# PM_Drive_UI.net
KiCad netlist of a schematic drawn in Altium Designer
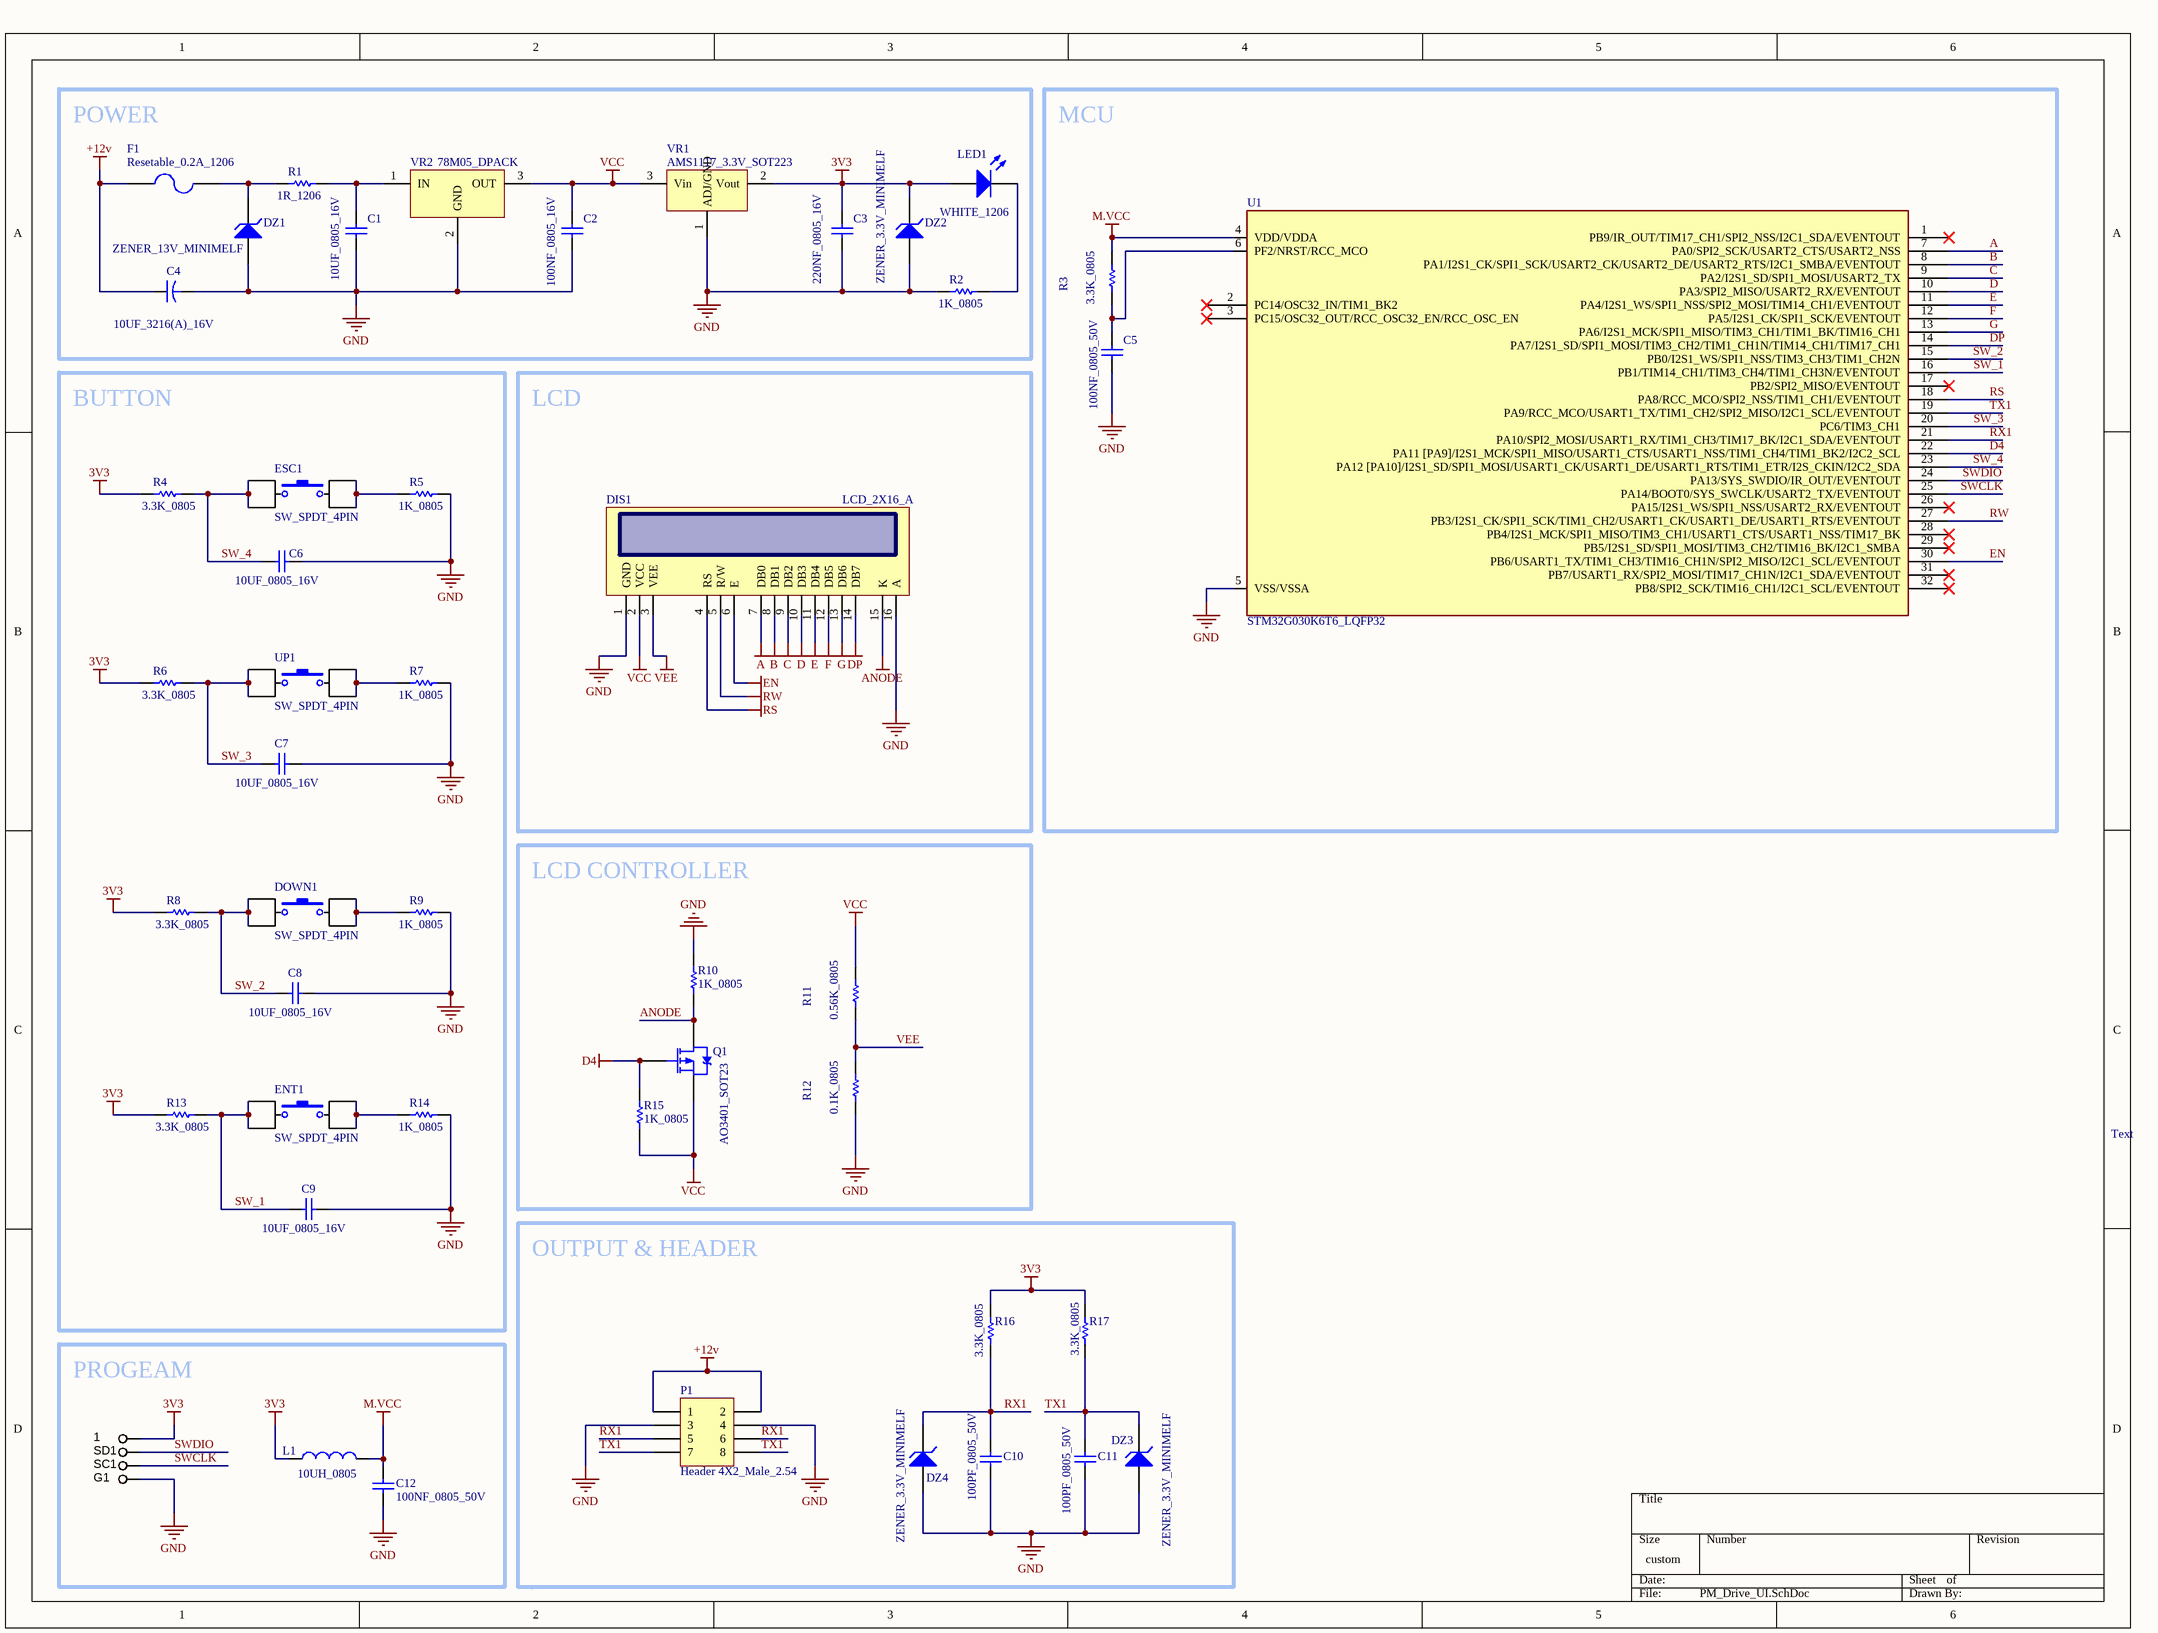
[diagram p0: PM_Drive_UI.SchDoc]

(export (version "E")
  (design (tool "Eeschema 10.0.6"))
  (components
    (comp (ref "1")
      (value "~")
      (footprint "TPSMD_D1")
      (description "TEST POINT")
      (fields (field (name "MANF") "MANF") (field (name "MANF_P#") "MANF_P#"))
      (libsource (lib "GTC Schematic") (part "TESTPOINT_SMD"))
    )
    (comp (ref "C1")
      (value "10UF_0805_16V")
      (footprint "Cap_0805_Nominal")
      (libsource (lib "Saeed_New_Lib") (part "Cap"))
    )
    (comp (ref "C2")
      (value "100NF_0805_16V")
      (footprint "Cap_0805_Nominal")
      (libsource (lib "Saeed_New_Lib") (part "Cap"))
    )
    (comp (ref "C3")
      (value "220NF_0805_16V")
      (footprint "Cap_0805_Nominal")
      (libsource (lib "Saeed_New_Lib") (part "Cap"))
    )
    (comp (ref "C4")
      (value "10UF_3216(A)_16V")
      (footprint "Cap_Tantal(3216)_A")
      (libsource (lib "GTC Shem") (part "Cap_Electrical"))
    )
    (comp (ref "C5")
      (value "100NF_0805_50V")
      (footprint "Cap_0805_Nominal")
      (libsource (lib "Saeed_New_Lib") (part "Cap"))
    )
    (comp (ref "C6")
      (value "10UF_0805_16V")
      (footprint "Cap_0805_Nominal")
      (libsource (lib "Saeed_New_Lib") (part "Cap"))
    )
    (comp (ref "C7")
      (value "10UF_0805_16V")
      (footprint "Cap_0805_Nominal")
      (libsource (lib "Saeed_New_Lib") (part "Cap"))
    )
    (comp (ref "C8")
      (value "10UF_0805_16V")
      (footprint "Cap_0805_Nominal")
      (libsource (lib "Saeed_New_Lib") (part "Cap"))
    )
    (comp (ref "C9")
      (value "10UF_0805_16V")
      (footprint "Cap_0805_Nominal")
      (libsource (lib "Saeed_New_Lib") (part "Cap"))
    )
    (comp (ref "C10")
      (value "100PF_0805_50V")
      (footprint "Cap_0805_Nominal")
      (libsource (lib "Saeed_New_Lib") (part "Cap"))
    )
    (comp (ref "C11")
      (value "100PF_0805_50V")
      (footprint "Cap_0805_Nominal")
      (libsource (lib "Saeed_New_Lib") (part "Cap"))
    )
    (comp (ref "C12")
      (value "100NF_0805_50V")
      (footprint "Cap_0805_Nominal")
      (libsource (lib "Saeed_New_Lib") (part "Cap"))
    )
    (comp (ref "DIS1")
      (value "LCD_2X16_A")
      (footprint "LCD_2X16_A")
      (libsource (lib "Amirreza") (part "LCD_2X16_A"))
    )
    (comp (ref "DOWN1")
      (value "SW_SPDT_4PIN")
      (footprint "SWPBS-DIP_6X6X13.5")
      (libsource (lib "Amirreza") (part "SW_SPDT_4PIN"))
    )
    (comp (ref "DZ1")
      (value "ZENER_13V_MINIMELF")
      (footprint "Diode_ZENER_MINIMELF")
      (libsource (lib "Amirreza") (part "Diode_Zener"))
    )
    (comp (ref "DZ2")
      (value "ZENER_3.3V_MINIMELF")
      (footprint "Diode_ZENER_MINIMELF")
      (libsource (lib "Amirreza") (part "Diode_Zener"))
    )
    (comp (ref "DZ3")
      (value "ZENER_3.3V_MINIMELF")
      (footprint "Diode_ZENER_MINIMELF")
      (libsource (lib "Amirreza") (part "Diode_Zener"))
    )
    (comp (ref "DZ4")
      (value "ZENER_3.3V_MINIMELF")
      (footprint "Diode_ZENER_MINIMELF")
      (libsource (lib "Amirreza") (part "Diode_Zener"))
    )
    (comp (ref "ENT1")
      (value "SW_SPDT_4PIN")
      (footprint "SWPBS-DIP_6X6X13.5")
      (libsource (lib "Amirreza") (part "SW_SPDT_4PIN"))
    )
    (comp (ref "ESC1")
      (value "SW_SPDT_4PIN")
      (footprint "SWPBS-DIP_6X6X13.5")
      (libsource (lib "Amirreza") (part "SW_SPDT_4PIN"))
    )
    (comp (ref "F1")
      (value "Resetable_0.2A_1206")
      (footprint "FUSE_1206")
      (libsource (lib "Amirreza") (part "FUSE"))
    )
    (comp (ref "G1")
      (value "~")
      (footprint "TPSMD_D1")
      (description "TEST POINT")
      (fields (field (name "MANF") "MANF") (field (name "MANF_P#") "MANF_P#"))
      (libsource (lib "GTC Schematic") (part "TESTPOINT_SMD"))
    )
    (comp (ref "L1")
      (value "10UH_0805")
      (footprint "INDUCTOR_0805_Nominal")
      (libsource (lib "Saeed_New_Lib") (part "Inductor"))
    )
    (comp (ref "LED1")
      (value "WHITE_1206")
      (footprint "LED_1206_NOMINAL")
      (libsource (lib "GTC Shem") (part "LED"))
    )
    (comp (ref "P1")
      (value "Header 4X2_Male_2.54")
      (footprint "HDR_M_2X4_2.54MM")
      (description "Header, 6-Pin, Dual row")
      (fields (field (name "PUBLISHER") "Altium Limited"))
      (libsource (lib "Amirreza") (part "Header 4X2"))
    )
    (comp (ref "Q1")
      (value "AO3401_SOT23")
      (footprint "SOT23_MOSFET")
      (description "P-Channel MOSFET")
      (fields (field (name "PUBLISHER") "Altium Limited"))
      (libsource (lib "Amirreza") (part "MOSFET-P"))
    )
    (comp (ref "R1")
      (value "1R_1206")
      (footprint "Res_1206_BIG SIZE")
      (libsource (lib "Amir_Library") (part "RES"))
    )
    (comp (ref "R2")
      (value "1K_0805")
      (footprint "Res_0805_Nominal")
      (libsource (lib "Amir_Library") (part "RES"))
    )
    (comp (ref "R3")
      (value "3.3K_0805")
      (footprint "Res_0805_Nominal")
      (libsource (lib "Amir_Library") (part "RES"))
    )
    (comp (ref "R4")
      (value "3.3K_0805")
      (footprint "Res_0805_Nominal")
      (libsource (lib "Amir_Library") (part "RES"))
    )
    (comp (ref "R5")
      (value "1K_0805")
      (footprint "Res_0805_Nominal")
      (libsource (lib "Amir_Library") (part "RES"))
    )
    (comp (ref "R6")
      (value "3.3K_0805")
      (footprint "Res_0805_Nominal")
      (libsource (lib "Amir_Library") (part "RES"))
    )
    (comp (ref "R7")
      (value "1K_0805")
      (footprint "Res_0805_Nominal")
      (libsource (lib "Amir_Library") (part "RES"))
    )
    (comp (ref "R8")
      (value "3.3K_0805")
      (footprint "Res_0805_Nominal")
      (libsource (lib "Amir_Library") (part "RES"))
    )
    (comp (ref "R9")
      (value "1K_0805")
      (footprint "Res_0805_Nominal")
      (libsource (lib "Amir_Library") (part "RES"))
    )
    (comp (ref "R10")
      (value "1K_0805")
      (footprint "Res_0805_Nominal")
      (libsource (lib "Amir_Library") (part "RES"))
    )
    (comp (ref "R11")
      (value "0.56K_0805")
      (footprint "Res_0805_Nominal")
      (libsource (lib "Amir_Library") (part "RES"))
    )
    (comp (ref "R12")
      (value "0.1K_0805")
      (footprint "Res_0805_Nominal")
      (libsource (lib "Amir_Library") (part "RES"))
    )
    (comp (ref "R13")
      (value "3.3K_0805")
      (footprint "Res_0805_Nominal")
      (libsource (lib "Amir_Library") (part "RES"))
    )
    (comp (ref "R14")
      (value "1K_0805")
      (footprint "Res_0805_Nominal")
      (libsource (lib "Amir_Library") (part "RES"))
    )
    (comp (ref "R15")
      (value "1K_0805")
      (footprint "Res_0805_Nominal")
      (libsource (lib "Amir_Library") (part "RES"))
    )
    (comp (ref "R16")
      (value "3.3K_0805")
      (footprint "Res_0805_Nominal")
      (libsource (lib "Amir_Library") (part "RES"))
    )
    (comp (ref "R17")
      (value "3.3K_0805")
      (footprint "Res_0805_Nominal")
      (libsource (lib "Amir_Library") (part "RES"))
    )
    (comp (ref "SC1")
      (value "~")
      (footprint "TPSMD_D1")
      (description "TEST POINT")
      (fields (field (name "MANF") "MANF") (field (name "MANF_P#") "MANF_P#"))
      (libsource (lib "GTC Schematic") (part "TESTPOINT_SMD"))
    )
    (comp (ref "SD1")
      (value "~")
      (footprint "TPSMD_D1")
      (description "TEST POINT")
      (fields (field (name "MANF") "MANF") (field (name "MANF_P#") "MANF_P#"))
      (libsource (lib "GTC Schematic") (part "TESTPOINT_SMD"))
    )
    (comp (ref "U1")
      (value "STM32G030K6T6_LQFP32")
      (footprint "QFG80_32")
      (fields (field (name "MANF") "ST") (field (name "MANF_P#") "STM32G030K6T6"))
      (libsource (lib "Amirreza") (part "STM32G030K6T6"))
    )
    (comp (ref "UP1")
      (value "SW_SPDT_4PIN")
      (footprint "SWPBS-DIP_6X6X13.5")
      (libsource (lib "Amirreza") (part "SW_SPDT_4PIN"))
    )
    (comp (ref "VR1")
      (value "AMS1117_3.3V_SOT223")
      (footprint "SOT223")
      (libsource (lib "Amirreza") (part "AMS1117"))
    )
    (comp (ref "VR2") (value "78M05_DPACK") (footprint "DPAK") (libsource (lib "Amirreza") (part "78M05")))
  )
  (nets
    (net (code "1") (name "+12v") (class "Default")
      (node (ref "C4") (pin "1") (pinfunction "1_1") (pintype "passive"))
      (node (ref "F1") (pin "1") (pinfunction "1_1") (pintype "passive"))
      (node (ref "P1") (pin "1") (pinfunction "1_1") (pintype "passive"))
      (node (ref "P1") (pin "2") (pinfunction "2_2") (pintype "passive"))
    )
    (net (code "2") (name "/RX1") (class "Default")
      (node (ref "C10") (pin "1") (pinfunction "1_1") (pintype "passive"))
      (node (ref "DZ4") (pin "2") (pinfunction "K_2") (pintype "passive"))
      (node (ref "P1") (pin "5") (pinfunction "5_5") (pintype "passive"))
      (node (ref "P1") (pin "6") (pinfunction "6_6") (pintype "passive"))
      (node (ref "R16") (pin "1") (pinfunction "1_1") (pintype "passive"))
      (node (ref "U1") (pin "21") (pinfunction "PA10/SPI2_MOSI/USART1_RX/TIM1_CH3/TIM17_BK/I2C1_SDA/EVENTOUT_21") (pintype "passive"))
    )
    (net (code "3") (name "/SWCLK") (class "Default")
      (node (ref "SC1") (pin "1") (pinfunction "1_1") (pintype "passive"))
      (node (ref "U1") (pin "25") (pinfunction "PA14/BOOT0/SYS_SWCLK/USART2_TX/EVENTOUT_25") (pintype "passive"))
    )
    (net (code "4") (name "/SWDIO") (class "Default")
      (node (ref "SD1") (pin "1") (pinfunction "1_1") (pintype "passive"))
      (node (ref "U1") (pin "24") (pinfunction "PA13/SYS_SWDIO/IR_OUT/EVENTOUT_24") (pintype "passive"))
    )
    (net (code "5") (name "/SW_1") (class "Default")
      (node (ref "C9") (pin "2") (pinfunction "2_2") (pintype "passive"))
      (node (ref "ENT1") (pin "1") (pinfunction "1_1") (pintype "passive"))
      (node (ref "ENT1") (pin "4") (pinfunction "4_4") (pintype "passive"))
      (node (ref "R13") (pin "2") (pinfunction "2_2") (pintype "passive"))
      (node (ref "U1") (pin "16") (pinfunction "PB1/TIM14_CH1/TIM3_CH4/TIM1_CH3N/EVENTOUT_16") (pintype "passive"))
    )
    (net (code "6") (name "/SW_2") (class "Default")
      (node (ref "C8") (pin "2") (pinfunction "2_2") (pintype "passive"))
      (node (ref "DOWN1") (pin "1") (pinfunction "1_1") (pintype "passive"))
      (node (ref "DOWN1") (pin "4") (pinfunction "4_4") (pintype "passive"))
      (node (ref "R8") (pin "2") (pinfunction "2_2") (pintype "passive"))
      (node (ref "U1") (pin "15") (pinfunction "PB0/I2S1_WS/SPI1_NSS/TIM3_CH3/TIM1_CH2N_15") (pintype "passive"))
    )
    (net (code "7") (name "/SW_3") (class "Default")
      (node (ref "C7") (pin "2") (pinfunction "2_2") (pintype "passive"))
      (node (ref "R6") (pin "2") (pinfunction "2_2") (pintype "passive"))
      (node (ref "U1") (pin "20") (pinfunction "PC6/TIM3_CH1_20") (pintype "passive"))
      (node (ref "UP1") (pin "1") (pinfunction "1_1") (pintype "passive"))
      (node (ref "UP1") (pin "4") (pinfunction "4_4") (pintype "passive"))
    )
    (net (code "8") (name "/SW_4") (class "Default")
      (node (ref "C6") (pin "2") (pinfunction "2_2") (pintype "passive"))
      (node (ref "ESC1") (pin "1") (pinfunction "1_1") (pintype "passive"))
      (node (ref "ESC1") (pin "4") (pinfunction "4_4") (pintype "passive"))
      (node (ref "R4") (pin "2") (pinfunction "2_2") (pintype "passive"))
      (node (ref "U1") (pin "23") (pinfunction "PA12_[PA10]/I2S1_SD/SPI1_MOSI/USART1_CK/USART1_DE/USART1_RTS/TIM1_ETR/I2S_CKIN/I2C2_SDA_23") (pintype "passive"))
    )
    (net (code "9") (name "/TX1") (class "Default")
      (node (ref "C11") (pin "1") (pinfunction "1_1") (pintype "passive"))
      (node (ref "DZ3") (pin "2") (pinfunction "K_2") (pintype "passive"))
      (node (ref "P1") (pin "7") (pinfunction "7_7") (pintype "passive"))
      (node (ref "P1") (pin "8") (pinfunction "8_8") (pintype "passive"))
      (node (ref "R17") (pin "1") (pinfunction "1_1") (pintype "passive"))
      (node (ref "U1") (pin "19") (pinfunction "PA9/RCC_MCO/USART1_TX/TIM1_CH2/SPI2_MISO/I2C1_SCL/EVENTOUT_19") (pintype "passive"))
    )
    (net (code "10") (name "3V3") (class "Default")
      (node (ref "1") (pin "1") (pinfunction "1_1") (pintype "passive"))
      (node (ref "C3") (pin "2") (pinfunction "2_2") (pintype "passive"))
      (node (ref "DZ2") (pin "2") (pinfunction "K_2") (pintype "passive"))
      (node (ref "L1") (pin "1") (pinfunction "1_1") (pintype "passive"))
      (node (ref "LED1") (pin "1") (pinfunction "A_1") (pintype "passive"))
      (node (ref "R13") (pin "1") (pinfunction "1_1") (pintype "passive"))
      (node (ref "R16") (pin "2") (pinfunction "2_2") (pintype "passive"))
      (node (ref "R17") (pin "2") (pinfunction "2_2") (pintype "passive"))
      (node (ref "R4") (pin "1") (pinfunction "1_1") (pintype "passive"))
      (node (ref "R6") (pin "1") (pinfunction "1_1") (pintype "passive"))
      (node (ref "R8") (pin "1") (pinfunction "1_1") (pintype "passive"))
      (node (ref "VR1") (pin "2") (pinfunction "Vout_2") (pintype "passive"))
    )
    (net (code "11") (name "A") (class "Default")
      (node (ref "DIS1") (pin "7") (pinfunction "DB0_7") (pintype "passive"))
      (node (ref "U1") (pin "7") (pinfunction "PA0/SPI2_SCK/USART2_CTS/USART2_NSS_7") (pintype "passive"))
    )
    (net (code "12") (name "ANODE") (class "Default")
      (node (ref "DIS1") (pin "15") (pinfunction "K_15") (pintype "passive"))
      (node (ref "Q1") (pin "3") (pinfunction "D_3") (pintype "passive"))
      (node (ref "R10") (pin "1") (pinfunction "1_1") (pintype "passive"))
    )
    (net (code "13") (name "B") (class "Default")
      (node (ref "DIS1") (pin "8") (pinfunction "DB1_8") (pintype "passive"))
      (node (ref "U1") (pin "8") (pinfunction "PA1/I2S1_CK/SPI1_SCK/USART2_CK/USART2_DE/USART2_RTS/I2C1_SMBA/EVENTOUT_8") (pintype "passive"))
    )
    (net (code "14") (name "C") (class "Default")
      (node (ref "DIS1") (pin "9") (pinfunction "DB2_9") (pintype "passive"))
      (node (ref "U1") (pin "9") (pinfunction "PA2/I2S1_SD/SPI1_MOSI/USART2_TX_9") (pintype "passive"))
    )
    (net (code "15") (name "D") (class "Default")
      (node (ref "DIS1") (pin "10") (pinfunction "DB3_10") (pintype "passive"))
      (node (ref "U1") (pin "10") (pinfunction "PA3/SPI2_MISO/USART2_RX/EVENTOUT_10") (pintype "passive"))
    )
    (net (code "16") (name "D4") (class "Default")
      (node (ref "Q1") (pin "1") (pinfunction "G_1") (pintype "passive"))
      (node (ref "R15") (pin "2") (pinfunction "2_2") (pintype "passive"))
      (node (ref "U1") (pin "22") (pinfunction "PA11_[PA9]/I2S1_MCK/SPI1_MISO/USART1_CTS/USART1_NSS/TIM1_CH4/TIM1_BK2/I2C2_SCL_22") (pintype "passive"))
    )
    (net (code "17") (name "DP") (class "Default")
      (node (ref "DIS1") (pin "14") (pinfunction "DB7_14") (pintype "passive"))
      (node (ref "U1") (pin "14") (pinfunction "PA7/I2S1_SD/SPI1_MOSI/TIM3_CH2/TIM1_CH1N/TIM14_CH1/TIM17_CH1_14") (pintype "passive"))
    )
    (net (code "18") (name "E") (class "Default")
      (node (ref "DIS1") (pin "11") (pinfunction "DB4_11") (pintype "passive"))
      (node (ref "U1") (pin "11") (pinfunction "PA4/I2S1_WS/SPI1_NSS/SPI2_MOSI/TIM14_CH1/EVENTOUT_11") (pintype "passive"))
    )
    (net (code "19") (name "EN") (class "Default")
      (node (ref "DIS1") (pin "6") (pinfunction "E_6") (pintype "passive"))
      (node (ref "U1") (pin "30") (pinfunction "PB6/USART1_TX/TIM1_CH3/TIM16_CH1N/SPI2_MISO/I2C1_SCL/EVENTOUT_30") (pintype "passive"))
    )
    (net (code "20") (name "F") (class "Default")
      (node (ref "DIS1") (pin "12") (pinfunction "DB5_12") (pintype "passive"))
      (node (ref "U1") (pin "12") (pinfunction "PA5/I2S1_CK/SPI1_SCK/EVENTOUT_12") (pintype "passive"))
    )
    (net (code "21") (name "G") (class "Default")
      (node (ref "DIS1") (pin "13") (pinfunction "DB6_13") (pintype "passive"))
      (node (ref "U1") (pin "13") (pinfunction "PA6/I2S1_MCK/SPI1_MISO/TIM3_CH1/TIM1_BK/TIM16_CH1_13") (pintype "passive"))
    )
    (net (code "22") (name "GND") (class "Default")
      (node (ref "C1") (pin "1") (pinfunction "1_1") (pintype "passive"))
      (node (ref "C10") (pin "2") (pinfunction "2_2") (pintype "passive"))
      (node (ref "C11") (pin "2") (pinfunction "2_2") (pintype "passive"))
      (node (ref "C12") (pin "2") (pinfunction "2_2") (pintype "passive"))
      (node (ref "C2") (pin "1") (pinfunction "1_1") (pintype "passive"))
      (node (ref "C3") (pin "1") (pinfunction "1_1") (pintype "passive"))
      (node (ref "C4") (pin "2") (pinfunction "2_2") (pintype "passive"))
      (node (ref "C5") (pin "1") (pinfunction "1_1") (pintype "passive"))
      (node (ref "C6") (pin "1") (pinfunction "1_1") (pintype "passive"))
      (node (ref "C7") (pin "1") (pinfunction "1_1") (pintype "passive"))
      (node (ref "C8") (pin "1") (pinfunction "1_1") (pintype "passive"))
      (node (ref "C9") (pin "1") (pinfunction "1_1") (pintype "passive"))
      (node (ref "DIS1") (pin "1") (pinfunction "GND_1") (pintype "passive"))
      (node (ref "DIS1") (pin "16") (pinfunction "A_16") (pintype "passive"))
      (node (ref "DZ1") (pin "1") (pinfunction "A_1") (pintype "passive"))
      (node (ref "DZ2") (pin "1") (pinfunction "A_1") (pintype "passive"))
      (node (ref "DZ3") (pin "1") (pinfunction "A_1") (pintype "passive"))
      (node (ref "DZ4") (pin "1") (pinfunction "A_1") (pintype "passive"))
      (node (ref "G1") (pin "1") (pinfunction "1_1") (pintype "passive"))
      (node (ref "P1") (pin "3") (pinfunction "3_3") (pintype "passive"))
      (node (ref "P1") (pin "4") (pinfunction "4_4") (pintype "passive"))
      (node (ref "R10") (pin "2") (pinfunction "2_2") (pintype "passive"))
      (node (ref "R12") (pin "1") (pinfunction "1_1") (pintype "passive"))
      (node (ref "R14") (pin "2") (pinfunction "2_2") (pintype "passive"))
      (node (ref "R2") (pin "1") (pinfunction "1_1") (pintype "passive"))
      (node (ref "R5") (pin "2") (pinfunction "2_2") (pintype "passive"))
      (node (ref "R7") (pin "2") (pinfunction "2_2") (pintype "passive"))
      (node (ref "R9") (pin "2") (pinfunction "2_2") (pintype "passive"))
      (node (ref "U1") (pin "5") (pinfunction "VSS/VSSA_5") (pintype "passive"))
      (node (ref "VR1") (pin "1") (pinfunction "ADJ/GND_1") (pintype "passive"))
      (node (ref "VR2") (pin "2") (pinfunction "GND_2") (pintype "passive"))
    )
    (net (code "23") (name "M.VCC") (class "Default")
      (node (ref "C12") (pin "1") (pinfunction "1_1") (pintype "passive"))
      (node (ref "L1") (pin "2") (pinfunction "2_2") (pintype "passive"))
      (node (ref "R3") (pin "2") (pinfunction "2_2") (pintype "passive"))
      (node (ref "U1") (pin "4") (pinfunction "VDD/VDDA_4") (pintype "passive"))
    )
    (net (code "24") (name "Net-(DOWN1-Pad2)") (class "Default")
      (node (ref "DOWN1") (pin "2") (pinfunction "2_2") (pintype "passive"))
      (node (ref "DOWN1") (pin "3") (pinfunction "3_3") (pintype "passive"))
      (node (ref "R9") (pin "1") (pinfunction "1_1") (pintype "passive"))
    )
    (net (code "25") (name "Net-(DZ1-K)") (class "Default")
      (node (ref "DZ1") (pin "2") (pinfunction "K_2") (pintype "passive"))
      (node (ref "F1") (pin "2") (pinfunction "2_2") (pintype "passive"))
      (node (ref "R1") (pin "1") (pinfunction "1_1") (pintype "passive"))
    )
    (net (code "26") (name "Net-(ENT1-Pad2)") (class "Default")
      (node (ref "ENT1") (pin "2") (pinfunction "2_2") (pintype "passive"))
      (node (ref "ENT1") (pin "3") (pinfunction "3_3") (pintype "passive"))
      (node (ref "R14") (pin "1") (pinfunction "1_1") (pintype "passive"))
    )
    (net (code "27") (name "Net-(ESC1-Pad2)") (class "Default")
      (node (ref "ESC1") (pin "2") (pinfunction "2_2") (pintype "passive"))
      (node (ref "ESC1") (pin "3") (pinfunction "3_3") (pintype "passive"))
      (node (ref "R5") (pin "1") (pinfunction "1_1") (pintype "passive"))
    )
    (net (code "28") (name "Net-(LED1-K)") (class "Default")
      (node (ref "LED1") (pin "2") (pinfunction "K_2") (pintype "passive"))
      (node (ref "R2") (pin "2") (pinfunction "2_2") (pintype "passive"))
    )
    (net (code "29") (name "Net-(R7-Pad1)") (class "Default")
      (node (ref "R7") (pin "1") (pinfunction "1_1") (pintype "passive"))
      (node (ref "UP1") (pin "2") (pinfunction "2_2") (pintype "passive"))
      (node (ref "UP1") (pin "3") (pinfunction "3_3") (pintype "passive"))
    )
    (net (code "30") (name "Net-(U1-PF2{slash}NRST{slash}RCC_MCO)") (class "Default")
      (node (ref "C5") (pin "2") (pinfunction "2_2") (pintype "passive"))
      (node (ref "R3") (pin "1") (pinfunction "1_1") (pintype "passive"))
      (node (ref "U1") (pin "6") (pinfunction "PF2/NRST/RCC_MCO_6") (pintype "passive"))
    )
    (net (code "31") (name "Net-(VR2-IN)") (class "Default")
      (node (ref "C1") (pin "2") (pinfunction "2_2") (pintype "passive"))
      (node (ref "R1") (pin "2") (pinfunction "2_2") (pintype "passive"))
      (node (ref "VR2") (pin "1") (pinfunction "IN_1") (pintype "passive"))
    )
    (net (code "32") (name "RS") (class "Default")
      (node (ref "DIS1") (pin "4") (pinfunction "RS_4") (pintype "passive"))
      (node (ref "U1") (pin "18") (pinfunction "PA8/RCC_MCO/SPI2_NSS/TIM1_CH1/EVENTOUT_18") (pintype "passive"))
    )
    (net (code "33") (name "RW") (class "Default")
      (node (ref "DIS1") (pin "5") (pinfunction "R/W_5") (pintype "passive"))
      (node (ref "U1") (pin "27") (pinfunction "PB3/I2S1_CK/SPI1_SCK/TIM1_CH2/USART1_CK/USART1_DE/USART1_RTS/EVENTOUT_27") (pintype "passive"))
    )
    (net (code "34") (name "VCC") (class "Default")
      (node (ref "C2") (pin "2") (pinfunction "2_2") (pintype "passive"))
      (node (ref "DIS1") (pin "2") (pinfunction "VCC_2") (pintype "passive"))
      (node (ref "Q1") (pin "2") (pinfunction "S_2") (pintype "passive"))
      (node (ref "R11") (pin "2") (pinfunction "2_2") (pintype "passive"))
      (node (ref "R15") (pin "1") (pinfunction "1_1") (pintype "passive"))
      (node (ref "VR1") (pin "3") (pinfunction "Vin_3") (pintype "passive"))
      (node (ref "VR2") (pin "3") (pinfunction "OUT_3") (pintype "passive"))
    )
    (net (code "35") (name "VEE") (class "Default")
      (node (ref "DIS1") (pin "3") (pinfunction "VEE_3") (pintype "passive"))
      (node (ref "R11") (pin "1") (pinfunction "1_1") (pintype "passive"))
      (node (ref "R12") (pin "2") (pinfunction "2_2") (pintype "passive"))
    )
    (net (code "36") (name "unconnected-(U1-PA15{slash}I2S1_WS{slash}SPI1_NSS{slash}USART2_RX{slash}EVENTOUT-Pad26)") (class "Default")
      (node (ref "U1") (pin "26") (pinfunction "PA15/I2S1_WS/SPI1_NSS/USART2_RX/EVENTOUT_26") (pintype "passive+no_connect"))
    )
    (net (code "37") (name "unconnected-(U1-PB2{slash}SPI2_MISO{slash}EVENTOUT-Pad17)") (class "Default")
      (node (ref "U1") (pin "17") (pinfunction "PB2/SPI2_MISO/EVENTOUT_17") (pintype "passive+no_connect"))
    )
    (net (code "38") (name "unconnected-(U1-PB4{slash}I2S1_MCK{slash}SPI1_MISO{slash}TIM3_CH1{slash}USART1_CTS{slash}USART1_NSS{slash}TIM17_BK-Pad28)") (class "Default")
      (node (ref "U1") (pin "28") (pinfunction "PB4/I2S1_MCK/SPI1_MISO/TIM3_CH1/USART1_CTS/USART1_NSS/TIM17_BK_28") (pintype "passive+no_connect"))
    )
    (net (code "39") (name "unconnected-(U1-PB5{slash}I2S1_SD{slash}SPI1_MOSI{slash}TIM3_CH2{slash}TIM16_BK{slash}I2C1_SMBA-Pad29)") (class "Default")
      (node (ref "U1") (pin "29") (pinfunction "PB5/I2S1_SD/SPI1_MOSI/TIM3_CH2/TIM16_BK/I2C1_SMBA_29") (pintype "passive+no_connect"))
    )
    (net (code "40") (name "unconnected-(U1-PB7{slash}USART1_RX{slash}SPI2_MOSI{slash}TIM17_CH1N{slash}I2C1_SDA{slash}EVENTOUT-Pad31)") (class "Default")
      (node (ref "U1") (pin "31") (pinfunction "PB7/USART1_RX/SPI2_MOSI/TIM17_CH1N/I2C1_SDA/EVENTOUT_31") (pintype "passive+no_connect"))
    )
    (net (code "41") (name "unconnected-(U1-PB8{slash}SPI2_SCK{slash}TIM16_CH1{slash}I2C1_SCL{slash}EVENTOUT-Pad32)") (class "Default")
      (node (ref "U1") (pin "32") (pinfunction "PB8/SPI2_SCK/TIM16_CH1/I2C1_SCL/EVENTOUT_32") (pintype "passive+no_connect"))
    )
    (net (code "42") (name "unconnected-(U1-PB9{slash}IR_OUT{slash}TIM17_CH1{slash}SPI2_NSS{slash}I2C1_SDA{slash}EVENTOUT-Pad1)") (class "Default")
      (node (ref "U1") (pin "1") (pinfunction "PB9/IR_OUT/TIM17_CH1/SPI2_NSS/I2C1_SDA/EVENTOUT_1") (pintype "passive+no_connect"))
    )
    (net (code "43") (name "unconnected-(U1-PC14{slash}OSC32_IN{slash}TIM1_BK2-Pad2)") (class "Default")
      (node (ref "U1") (pin "2") (pinfunction "PC14/OSC32_IN/TIM1_BK2_2") (pintype "passive+no_connect"))
    )
    (net (code "44") (name "unconnected-(U1-PC15{slash}OSC32_OUT{slash}RCC_OSC32_EN{slash}RCC_OSC_EN-Pad3)") (class "Default")
      (node (ref "U1") (pin "3") (pinfunction "PC15/OSC32_OUT/RCC_OSC32_EN/RCC_OSC_EN_3") (pintype "passive+no_connect"))
    )
  )
)
